# HighVBoard_01.net
KiCad netlist of a schematic drawn in EAGLE
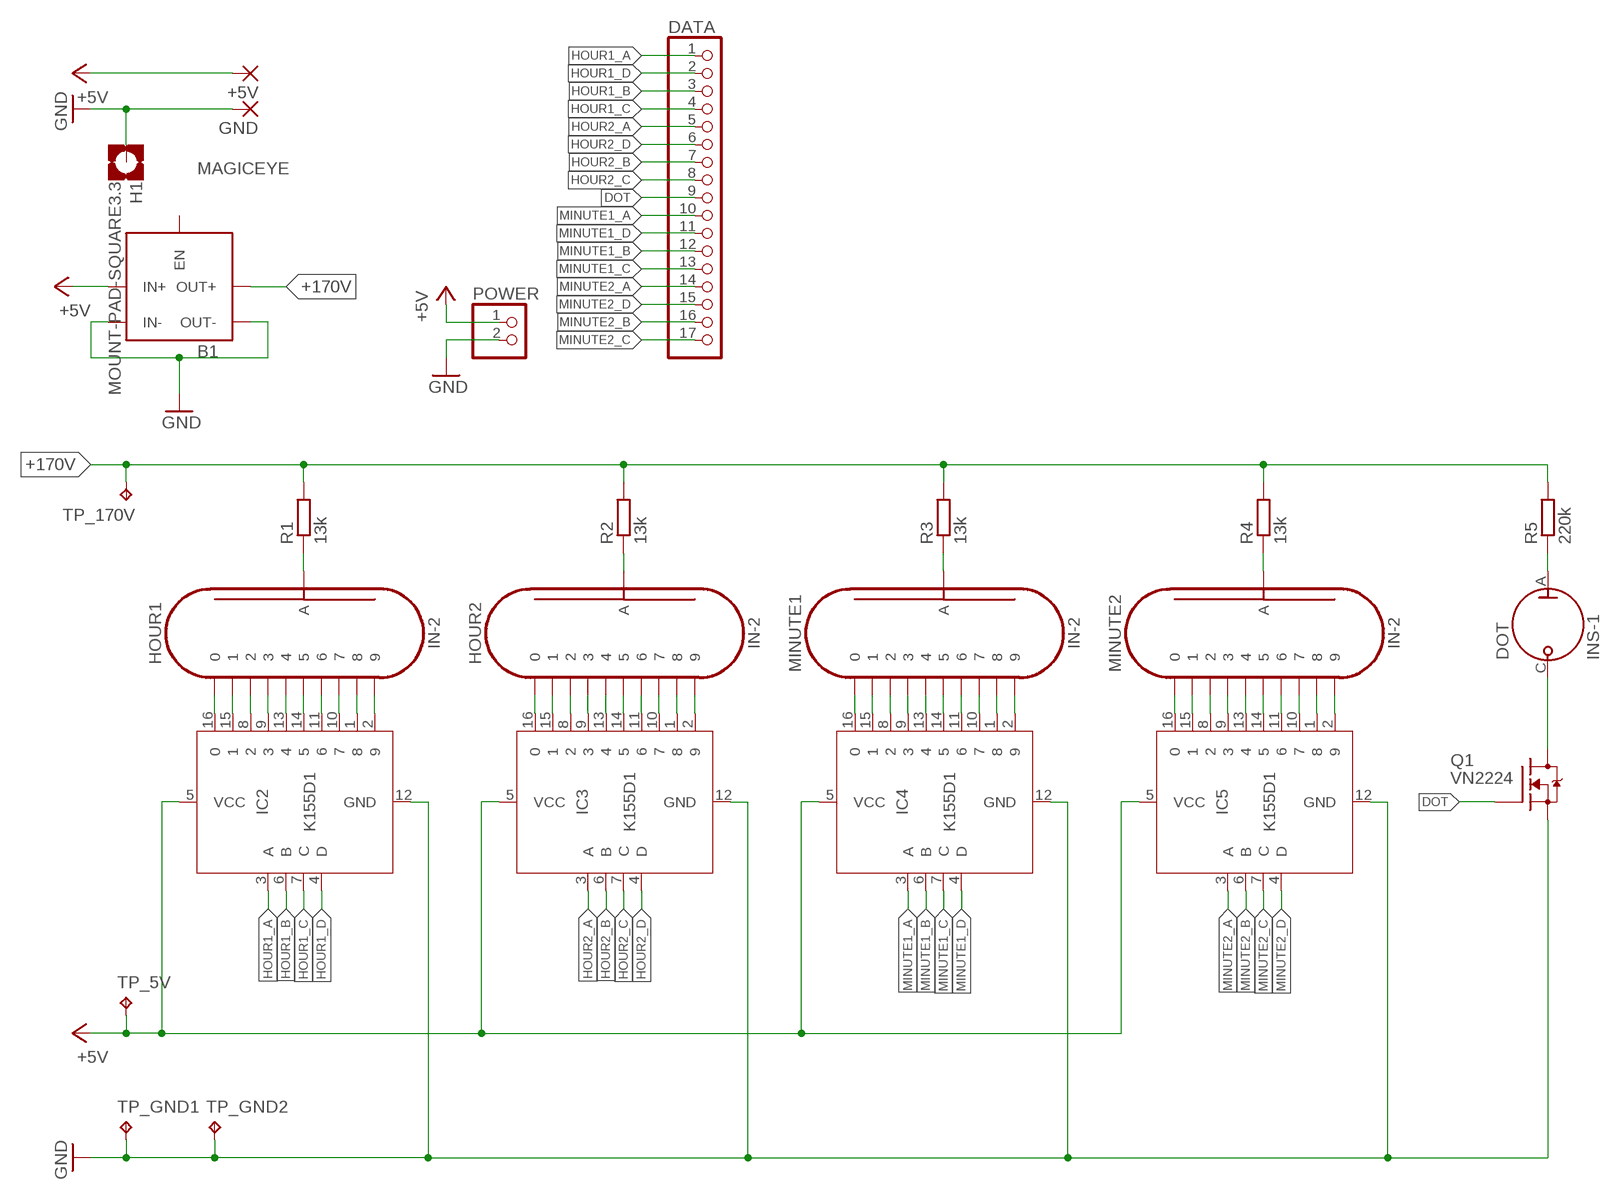
[diagram p0: schematic, sheet 1]

(export (version "E")
  (design (tool "Eeschema 10.0.6"))
  (components
    (comp (ref "+5V")
      (value "2,15/1,0")
      (footprint "eagle-import:2,15_1,0")
      (libsource (lib "eagle-import") (part "2,15/1,0"))
    )
    (comp (ref "B1")
      (value "MAGICEYE")
      (footprint "eagle-import:MAGICEYE")
      (libsource (lib "eagle-import") (part "MAGICEYE"))
    )
    (comp (ref "DATA")
      (value "PINHD-1X17")
      (footprint "eagle-import:1X17")
      (libsource (lib "eagle-import") (part "PINHD-1X17"))
    )
    (comp (ref "DOT")
      (value "INS-1")
      (footprint "eagle-import:INS-1")
      (libsource (lib "eagle-import") (part "INS-1"))
    )
    (comp (ref "GND")
      (value "2,15/1,0")
      (footprint "eagle-import:2,15_1,0")
      (libsource (lib "eagle-import") (part "2,15/1,0"))
    )
    (comp (ref "H1")
      (value "MOUNT-PAD-SQUARE3.3")
      (footprint "eagle-import:3,3-PAD-SQUARE")
      (libsource (lib "eagle-import") (part "MOUNT-PAD-SQUARE3.3"))
    )
    (comp (ref "HOUR1")
      (value "IN-2")
      (footprint "eagle-import:IN-2")
      (libsource (lib "eagle-import") (part "IN-2"))
    )
    (comp (ref "HOUR2")
      (value "IN-2")
      (footprint "eagle-import:IN-2")
      (libsource (lib "eagle-import") (part "IN-2"))
    )
    (comp (ref "IC2")
      (value "K155D1")
      (footprint "eagle-import:DIL16")
      (libsource (lib "eagle-import") (part "K155D1"))
    )
    (comp (ref "IC3")
      (value "K155D1")
      (footprint "eagle-import:DIL16")
      (libsource (lib "eagle-import") (part "K155D1"))
    )
    (comp (ref "IC4")
      (value "K155D1")
      (footprint "eagle-import:DIL16")
      (libsource (lib "eagle-import") (part "K155D1"))
    )
    (comp (ref "IC5")
      (value "K155D1")
      (footprint "eagle-import:DIL16")
      (libsource (lib "eagle-import") (part "K155D1"))
    )
    (comp (ref "MINUTE1")
      (value "IN-2")
      (footprint "eagle-import:IN-2")
      (libsource (lib "eagle-import") (part "IN-2"))
    )
    (comp (ref "MINUTE2")
      (value "IN-2")
      (footprint "eagle-import:IN-2")
      (libsource (lib "eagle-import") (part "IN-2"))
    )
    (comp (ref "POWER")
      (value "PINHD-1X2")
      (footprint "eagle-import:1X02")
      (libsource (lib "eagle-import") (part "PINHD-1X2"))
    )
    (comp (ref "Q1")
      (value "VN2224")
      (footprint "eagle-import:TO92")
      (libsource (lib "eagle-import") (part "VN2224"))
    )
    (comp (ref "R1")
      (value "13k")
      (footprint "eagle-import:0207_10")
      (libsource (lib "eagle-import") (part "R-EU_0207/10"))
    )
    (comp (ref "R2")
      (value "13k")
      (footprint "eagle-import:0207_10")
      (libsource (lib "eagle-import") (part "R-EU_0207/10"))
    )
    (comp (ref "R3")
      (value "13k")
      (footprint "eagle-import:0207_10")
      (libsource (lib "eagle-import") (part "R-EU_0207/10"))
    )
    (comp (ref "R4")
      (value "13k")
      (footprint "eagle-import:0207_10")
      (libsource (lib "eagle-import") (part "R-EU_0207/10"))
    )
    (comp (ref "R5")
      (value "220k")
      (footprint "eagle-import:0207_10")
      (libsource (lib "eagle-import") (part "R-EU_0207/10"))
    )
    (comp (ref "TP_5V")
      (value "TPPAD1-13")
      (footprint "eagle-import:P1-13")
      (libsource (lib "eagle-import") (part "TPPAD1-13"))
    )
    (comp (ref "TP_170V")
      (value "TPPAD1-13")
      (footprint "eagle-import:P1-13")
      (libsource (lib "eagle-import") (part "TPPAD1-13"))
    )
    (comp (ref "TP_GND1")
      (value "TPPAD1-13")
      (footprint "eagle-import:P1-13")
      (libsource (lib "eagle-import") (part "TPPAD1-13"))
    )
    (comp (ref "TP_GND2")
      (value "TPPAD1-13")
      (footprint "eagle-import:P1-13")
      (libsource (lib "eagle-import") (part "TPPAD1-13"))
    )
  )
  (nets
    (net (code "1") (name "+5V") (class "Default")
      (node (ref "+5V") (pin "1") (pinfunction "P_1") (pintype "passive"))
      (node (ref "B1") (pin "IN+") (pinfunction "IN+_IN+") (pintype "bidirectional"))
      (node (ref "IC2") (pin "5") (pinfunction "VCC_5") (pintype "bidirectional"))
      (node (ref "IC3") (pin "5") (pinfunction "VCC_5") (pintype "bidirectional"))
      (node (ref "IC4") (pin "5") (pinfunction "VCC_5") (pintype "bidirectional"))
      (node (ref "IC5") (pin "5") (pinfunction "VCC_5") (pintype "bidirectional"))
      (node (ref "POWER") (pin "1") (pinfunction "1_1") (pintype "passive"))
      (node (ref "TP_5V") (pin "TP") (pinfunction "TP_TP") (pintype "input"))
    )
    (net (code "2") (name "+170V") (class "Default")
      (node (ref "B1") (pin "OUT+") (pinfunction "OUT+_OUT+") (pintype "bidirectional"))
      (node (ref "R1") (pin "2") (pinfunction "2_2") (pintype "passive"))
      (node (ref "R2") (pin "2") (pinfunction "2_2") (pintype "passive"))
      (node (ref "R3") (pin "2") (pinfunction "2_2") (pintype "passive"))
      (node (ref "R4") (pin "2") (pinfunction "2_2") (pintype "passive"))
      (node (ref "R5") (pin "2") (pinfunction "2_2") (pintype "passive"))
      (node (ref "TP_170V") (pin "TP") (pinfunction "TP_TP") (pintype "input"))
    )
    (net (code "3") (name "DOT") (class "Default")
      (node (ref "DATA") (pin "9") (pinfunction "9_9") (pintype "passive"))
      (node (ref "Q1") (pin "2") (pinfunction "G_2") (pintype "passive"))
    )
    (net (code "4") (name "GND") (class "Default")
      (node (ref "B1") (pin "IN-") (pinfunction "IN-_IN-") (pintype "bidirectional"))
      (node (ref "B1") (pin "OUT-") (pinfunction "OUT-_OUT-") (pintype "bidirectional"))
      (node (ref "GND") (pin "1") (pinfunction "P_1") (pintype "passive"))
      (node (ref "H1") (pin "B3,3") (pinfunction "MOUNT_B3,3") (pintype "passive"))
      (node (ref "IC2") (pin "12") (pinfunction "GND_12") (pintype "bidirectional"))
      (node (ref "IC3") (pin "12") (pinfunction "GND_12") (pintype "bidirectional"))
      (node (ref "IC4") (pin "12") (pinfunction "GND_12") (pintype "bidirectional"))
      (node (ref "IC5") (pin "12") (pinfunction "GND_12") (pintype "bidirectional"))
      (node (ref "POWER") (pin "2") (pinfunction "2_2") (pintype "passive"))
      (node (ref "Q1") (pin "1") (pinfunction "S_1") (pintype "passive"))
      (node (ref "TP_GND1") (pin "TP") (pinfunction "TP_TP") (pintype "input"))
      (node (ref "TP_GND2") (pin "TP") (pinfunction "TP_TP") (pintype "input"))
    )
    (net (code "5") (name "HOUR1_A") (class "Default")
      (node (ref "DATA") (pin "1") (pinfunction "1_1") (pintype "passive"))
      (node (ref "IC2") (pin "3") (pinfunction "A_3") (pintype "bidirectional"))
    )
    (net (code "6") (name "HOUR1_B") (class "Default")
      (node (ref "DATA") (pin "3") (pinfunction "3_3") (pintype "passive"))
      (node (ref "IC2") (pin "6") (pinfunction "B_6") (pintype "bidirectional"))
    )
    (net (code "7") (name "HOUR1_C") (class "Default")
      (node (ref "DATA") (pin "4") (pinfunction "4_4") (pintype "passive"))
      (node (ref "IC2") (pin "7") (pinfunction "C_7") (pintype "bidirectional"))
    )
    (net (code "8") (name "HOUR1_D") (class "Default")
      (node (ref "DATA") (pin "2") (pinfunction "2_2") (pintype "passive"))
      (node (ref "IC2") (pin "4") (pinfunction "D_4") (pintype "bidirectional"))
    )
    (net (code "9") (name "HOUR2_A") (class "Default")
      (node (ref "DATA") (pin "5") (pinfunction "5_5") (pintype "passive"))
      (node (ref "IC3") (pin "3") (pinfunction "A_3") (pintype "bidirectional"))
    )
    (net (code "10") (name "HOUR2_B") (class "Default")
      (node (ref "DATA") (pin "7") (pinfunction "7_7") (pintype "passive"))
      (node (ref "IC3") (pin "6") (pinfunction "B_6") (pintype "bidirectional"))
    )
    (net (code "11") (name "HOUR2_C") (class "Default")
      (node (ref "DATA") (pin "8") (pinfunction "8_8") (pintype "passive"))
      (node (ref "IC3") (pin "7") (pinfunction "C_7") (pintype "bidirectional"))
    )
    (net (code "12") (name "HOUR2_D") (class "Default")
      (node (ref "DATA") (pin "6") (pinfunction "6_6") (pintype "passive"))
      (node (ref "IC3") (pin "4") (pinfunction "D_4") (pintype "bidirectional"))
    )
    (net (code "13") (name "MINUTE1_A") (class "Default")
      (node (ref "DATA") (pin "10") (pinfunction "10_10") (pintype "passive"))
      (node (ref "IC4") (pin "3") (pinfunction "A_3") (pintype "bidirectional"))
    )
    (net (code "14") (name "MINUTE1_B") (class "Default")
      (node (ref "DATA") (pin "12") (pinfunction "12_12") (pintype "passive"))
      (node (ref "IC4") (pin "6") (pinfunction "B_6") (pintype "bidirectional"))
    )
    (net (code "15") (name "MINUTE1_C") (class "Default")
      (node (ref "DATA") (pin "13") (pinfunction "13_13") (pintype "passive"))
      (node (ref "IC4") (pin "7") (pinfunction "C_7") (pintype "bidirectional"))
    )
    (net (code "16") (name "MINUTE1_D") (class "Default")
      (node (ref "DATA") (pin "11") (pinfunction "11_11") (pintype "passive"))
      (node (ref "IC4") (pin "4") (pinfunction "D_4") (pintype "bidirectional"))
    )
    (net (code "17") (name "MINUTE2_A") (class "Default")
      (node (ref "DATA") (pin "14") (pinfunction "14_14") (pintype "passive"))
      (node (ref "IC5") (pin "3") (pinfunction "A_3") (pintype "bidirectional"))
    )
    (net (code "18") (name "MINUTE2_B") (class "Default")
      (node (ref "DATA") (pin "16") (pinfunction "16_16") (pintype "passive"))
      (node (ref "IC5") (pin "6") (pinfunction "B_6") (pintype "bidirectional"))
    )
    (net (code "19") (name "MINUTE2_C") (class "Default")
      (node (ref "DATA") (pin "17") (pinfunction "17_17") (pintype "passive"))
      (node (ref "IC5") (pin "7") (pinfunction "C_7") (pintype "bidirectional"))
    )
    (net (code "20") (name "MINUTE2_D") (class "Default")
      (node (ref "DATA") (pin "15") (pinfunction "15_15") (pintype "passive"))
      (node (ref "IC5") (pin "4") (pinfunction "D_4") (pintype "bidirectional"))
    )
    (net (code "21") (name "Net-(DOT-PadA)") (class "Default")
      (node (ref "DOT") (pin "A") (pinfunction "A_A") (pintype "bidirectional"))
      (node (ref "R5") (pin "1") (pinfunction "1_1") (pintype "passive"))
    )
    (net (code "22") (name "Net-(HOUR1-PadA)") (class "Default")
      (node (ref "HOUR1") (pin "A") (pinfunction "A_A") (pintype "bidirectional"))
      (node (ref "R1") (pin "1") (pinfunction "1_1") (pintype "passive"))
    )
    (net (code "23") (name "Net-(HOUR2-PadA)") (class "Default")
      (node (ref "HOUR2") (pin "A") (pinfunction "A_A") (pintype "bidirectional"))
      (node (ref "R2") (pin "1") (pinfunction "1_1") (pintype "passive"))
    )
    (net (code "24") (name "Net-(IC2-0)") (class "Default")
      (node (ref "HOUR1") (pin "0") (pinfunction "0_0") (pintype "bidirectional"))
      (node (ref "IC2") (pin "16") (pinfunction "0_16") (pintype "bidirectional"))
    )
    (net (code "25") (name "Net-(IC2-1)") (class "Default")
      (node (ref "HOUR1") (pin "1") (pinfunction "1_1") (pintype "bidirectional"))
      (node (ref "IC2") (pin "15") (pinfunction "1_15") (pintype "bidirectional"))
    )
    (net (code "26") (name "Net-(IC2-2)") (class "Default")
      (node (ref "HOUR1") (pin "2") (pinfunction "2_2") (pintype "bidirectional"))
      (node (ref "IC2") (pin "8") (pinfunction "2_8") (pintype "bidirectional"))
    )
    (net (code "27") (name "Net-(IC2-3)") (class "Default")
      (node (ref "HOUR1") (pin "3") (pinfunction "3_3") (pintype "bidirectional"))
      (node (ref "IC2") (pin "9") (pinfunction "3_9") (pintype "bidirectional"))
    )
    (net (code "28") (name "Net-(IC2-4)") (class "Default")
      (node (ref "HOUR1") (pin "4") (pinfunction "4_4") (pintype "bidirectional"))
      (node (ref "IC2") (pin "13") (pinfunction "4_13") (pintype "bidirectional"))
    )
    (net (code "29") (name "Net-(IC2-5)") (class "Default")
      (node (ref "HOUR1") (pin "5") (pinfunction "5_5") (pintype "bidirectional"))
      (node (ref "IC2") (pin "14") (pinfunction "5_14") (pintype "bidirectional"))
    )
    (net (code "30") (name "Net-(IC2-6)") (class "Default")
      (node (ref "HOUR1") (pin "6") (pinfunction "6_6") (pintype "bidirectional"))
      (node (ref "IC2") (pin "11") (pinfunction "6_11") (pintype "bidirectional"))
    )
    (net (code "31") (name "Net-(IC2-7)") (class "Default")
      (node (ref "HOUR1") (pin "7") (pinfunction "7_7") (pintype "bidirectional"))
      (node (ref "IC2") (pin "10") (pinfunction "7_10") (pintype "bidirectional"))
    )
    (net (code "32") (name "Net-(IC2-8)") (class "Default")
      (node (ref "HOUR1") (pin "8") (pinfunction "8_8") (pintype "bidirectional"))
      (node (ref "IC2") (pin "1") (pinfunction "8_1") (pintype "bidirectional"))
    )
    (net (code "33") (name "Net-(IC2-9)") (class "Default")
      (node (ref "HOUR1") (pin "9") (pinfunction "9_9") (pintype "bidirectional"))
      (node (ref "IC2") (pin "2") (pinfunction "9_2") (pintype "bidirectional"))
    )
    (net (code "34") (name "Net-(IC3-0)") (class "Default")
      (node (ref "HOUR2") (pin "0") (pinfunction "0_0") (pintype "bidirectional"))
      (node (ref "IC3") (pin "16") (pinfunction "0_16") (pintype "bidirectional"))
    )
    (net (code "35") (name "Net-(IC3-1)") (class "Default")
      (node (ref "HOUR2") (pin "1") (pinfunction "1_1") (pintype "bidirectional"))
      (node (ref "IC3") (pin "15") (pinfunction "1_15") (pintype "bidirectional"))
    )
    (net (code "36") (name "Net-(IC3-2)") (class "Default")
      (node (ref "HOUR2") (pin "2") (pinfunction "2_2") (pintype "bidirectional"))
      (node (ref "IC3") (pin "8") (pinfunction "2_8") (pintype "bidirectional"))
    )
    (net (code "37") (name "Net-(IC3-3)") (class "Default")
      (node (ref "HOUR2") (pin "3") (pinfunction "3_3") (pintype "bidirectional"))
      (node (ref "IC3") (pin "9") (pinfunction "3_9") (pintype "bidirectional"))
    )
    (net (code "38") (name "Net-(IC3-4)") (class "Default")
      (node (ref "HOUR2") (pin "4") (pinfunction "4_4") (pintype "bidirectional"))
      (node (ref "IC3") (pin "13") (pinfunction "4_13") (pintype "bidirectional"))
    )
    (net (code "39") (name "Net-(IC3-5)") (class "Default")
      (node (ref "HOUR2") (pin "5") (pinfunction "5_5") (pintype "bidirectional"))
      (node (ref "IC3") (pin "14") (pinfunction "5_14") (pintype "bidirectional"))
    )
    (net (code "40") (name "Net-(IC3-6)") (class "Default")
      (node (ref "HOUR2") (pin "6") (pinfunction "6_6") (pintype "bidirectional"))
      (node (ref "IC3") (pin "11") (pinfunction "6_11") (pintype "bidirectional"))
    )
    (net (code "41") (name "Net-(IC3-7)") (class "Default")
      (node (ref "HOUR2") (pin "7") (pinfunction "7_7") (pintype "bidirectional"))
      (node (ref "IC3") (pin "10") (pinfunction "7_10") (pintype "bidirectional"))
    )
    (net (code "42") (name "Net-(IC3-8)") (class "Default")
      (node (ref "HOUR2") (pin "8") (pinfunction "8_8") (pintype "bidirectional"))
      (node (ref "IC3") (pin "1") (pinfunction "8_1") (pintype "bidirectional"))
    )
    (net (code "43") (name "Net-(IC3-9)") (class "Default")
      (node (ref "HOUR2") (pin "9") (pinfunction "9_9") (pintype "bidirectional"))
      (node (ref "IC3") (pin "2") (pinfunction "9_2") (pintype "bidirectional"))
    )
    (net (code "44") (name "Net-(IC4-0)") (class "Default")
      (node (ref "IC4") (pin "16") (pinfunction "0_16") (pintype "bidirectional"))
      (node (ref "MINUTE1") (pin "0") (pinfunction "0_0") (pintype "bidirectional"))
    )
    (net (code "45") (name "Net-(IC4-1)") (class "Default")
      (node (ref "IC4") (pin "15") (pinfunction "1_15") (pintype "bidirectional"))
      (node (ref "MINUTE1") (pin "1") (pinfunction "1_1") (pintype "bidirectional"))
    )
    (net (code "46") (name "Net-(IC4-2)") (class "Default")
      (node (ref "IC4") (pin "8") (pinfunction "2_8") (pintype "bidirectional"))
      (node (ref "MINUTE1") (pin "2") (pinfunction "2_2") (pintype "bidirectional"))
    )
    (net (code "47") (name "Net-(IC4-3)") (class "Default")
      (node (ref "IC4") (pin "9") (pinfunction "3_9") (pintype "bidirectional"))
      (node (ref "MINUTE1") (pin "3") (pinfunction "3_3") (pintype "bidirectional"))
    )
    (net (code "48") (name "Net-(IC4-4)") (class "Default")
      (node (ref "IC4") (pin "13") (pinfunction "4_13") (pintype "bidirectional"))
      (node (ref "MINUTE1") (pin "4") (pinfunction "4_4") (pintype "bidirectional"))
    )
    (net (code "49") (name "Net-(IC4-5)") (class "Default")
      (node (ref "IC4") (pin "14") (pinfunction "5_14") (pintype "bidirectional"))
      (node (ref "MINUTE1") (pin "5") (pinfunction "5_5") (pintype "bidirectional"))
    )
    (net (code "50") (name "Net-(IC4-6)") (class "Default")
      (node (ref "IC4") (pin "11") (pinfunction "6_11") (pintype "bidirectional"))
      (node (ref "MINUTE1") (pin "6") (pinfunction "6_6") (pintype "bidirectional"))
    )
    (net (code "51") (name "Net-(IC4-7)") (class "Default")
      (node (ref "IC4") (pin "10") (pinfunction "7_10") (pintype "bidirectional"))
      (node (ref "MINUTE1") (pin "7") (pinfunction "7_7") (pintype "bidirectional"))
    )
    (net (code "52") (name "Net-(IC4-8)") (class "Default")
      (node (ref "IC4") (pin "1") (pinfunction "8_1") (pintype "bidirectional"))
      (node (ref "MINUTE1") (pin "8") (pinfunction "8_8") (pintype "bidirectional"))
    )
    (net (code "53") (name "Net-(IC4-9)") (class "Default")
      (node (ref "IC4") (pin "2") (pinfunction "9_2") (pintype "bidirectional"))
      (node (ref "MINUTE1") (pin "9") (pinfunction "9_9") (pintype "bidirectional"))
    )
    (net (code "54") (name "Net-(IC5-0)") (class "Default")
      (node (ref "IC5") (pin "16") (pinfunction "0_16") (pintype "bidirectional"))
      (node (ref "MINUTE2") (pin "0") (pinfunction "0_0") (pintype "bidirectional"))
    )
    (net (code "55") (name "Net-(IC5-1)") (class "Default")
      (node (ref "IC5") (pin "15") (pinfunction "1_15") (pintype "bidirectional"))
      (node (ref "MINUTE2") (pin "1") (pinfunction "1_1") (pintype "bidirectional"))
    )
    (net (code "56") (name "Net-(IC5-2)") (class "Default")
      (node (ref "IC5") (pin "8") (pinfunction "2_8") (pintype "bidirectional"))
      (node (ref "MINUTE2") (pin "2") (pinfunction "2_2") (pintype "bidirectional"))
    )
    (net (code "57") (name "Net-(IC5-3)") (class "Default")
      (node (ref "IC5") (pin "9") (pinfunction "3_9") (pintype "bidirectional"))
      (node (ref "MINUTE2") (pin "3") (pinfunction "3_3") (pintype "bidirectional"))
    )
    (net (code "58") (name "Net-(IC5-4)") (class "Default")
      (node (ref "IC5") (pin "13") (pinfunction "4_13") (pintype "bidirectional"))
      (node (ref "MINUTE2") (pin "4") (pinfunction "4_4") (pintype "bidirectional"))
    )
    (net (code "59") (name "Net-(IC5-5)") (class "Default")
      (node (ref "IC5") (pin "14") (pinfunction "5_14") (pintype "bidirectional"))
      (node (ref "MINUTE2") (pin "5") (pinfunction "5_5") (pintype "bidirectional"))
    )
    (net (code "60") (name "Net-(IC5-6)") (class "Default")
      (node (ref "IC5") (pin "11") (pinfunction "6_11") (pintype "bidirectional"))
      (node (ref "MINUTE2") (pin "6") (pinfunction "6_6") (pintype "bidirectional"))
    )
    (net (code "61") (name "Net-(IC5-7)") (class "Default")
      (node (ref "IC5") (pin "10") (pinfunction "7_10") (pintype "bidirectional"))
      (node (ref "MINUTE2") (pin "7") (pinfunction "7_7") (pintype "bidirectional"))
    )
    (net (code "62") (name "Net-(IC5-8)") (class "Default")
      (node (ref "IC5") (pin "1") (pinfunction "8_1") (pintype "bidirectional"))
      (node (ref "MINUTE2") (pin "8") (pinfunction "8_8") (pintype "bidirectional"))
    )
    (net (code "63") (name "Net-(IC5-9)") (class "Default")
      (node (ref "IC5") (pin "2") (pinfunction "9_2") (pintype "bidirectional"))
      (node (ref "MINUTE2") (pin "9") (pinfunction "9_9") (pintype "bidirectional"))
    )
    (net (code "64") (name "Net-(MINUTE1-PadA)") (class "Default")
      (node (ref "MINUTE1") (pin "A") (pinfunction "A_A") (pintype "bidirectional"))
      (node (ref "R3") (pin "1") (pinfunction "1_1") (pintype "passive"))
    )
    (net (code "65") (name "Net-(MINUTE2-PadA)") (class "Default")
      (node (ref "MINUTE2") (pin "A") (pinfunction "A_A") (pintype "bidirectional"))
      (node (ref "R4") (pin "1") (pinfunction "1_1") (pintype "passive"))
    )
    (net (code "66") (name "Net-(Q1-D)") (class "Default")
      (node (ref "DOT") (pin "C") (pinfunction "C_C") (pintype "bidirectional"))
      (node (ref "Q1") (pin "3") (pinfunction "D_3") (pintype "passive"))
    )
    (net (code "67") (name "unconnected-(B1-PadEN)") (class "Default")
      (node (ref "B1") (pin "EN") (pinfunction "EN_EN") (pintype "bidirectional"))
    )
  )
)
